# LDO_3V3.net
KiCad netlist of a schematic drawn in Altium Designer
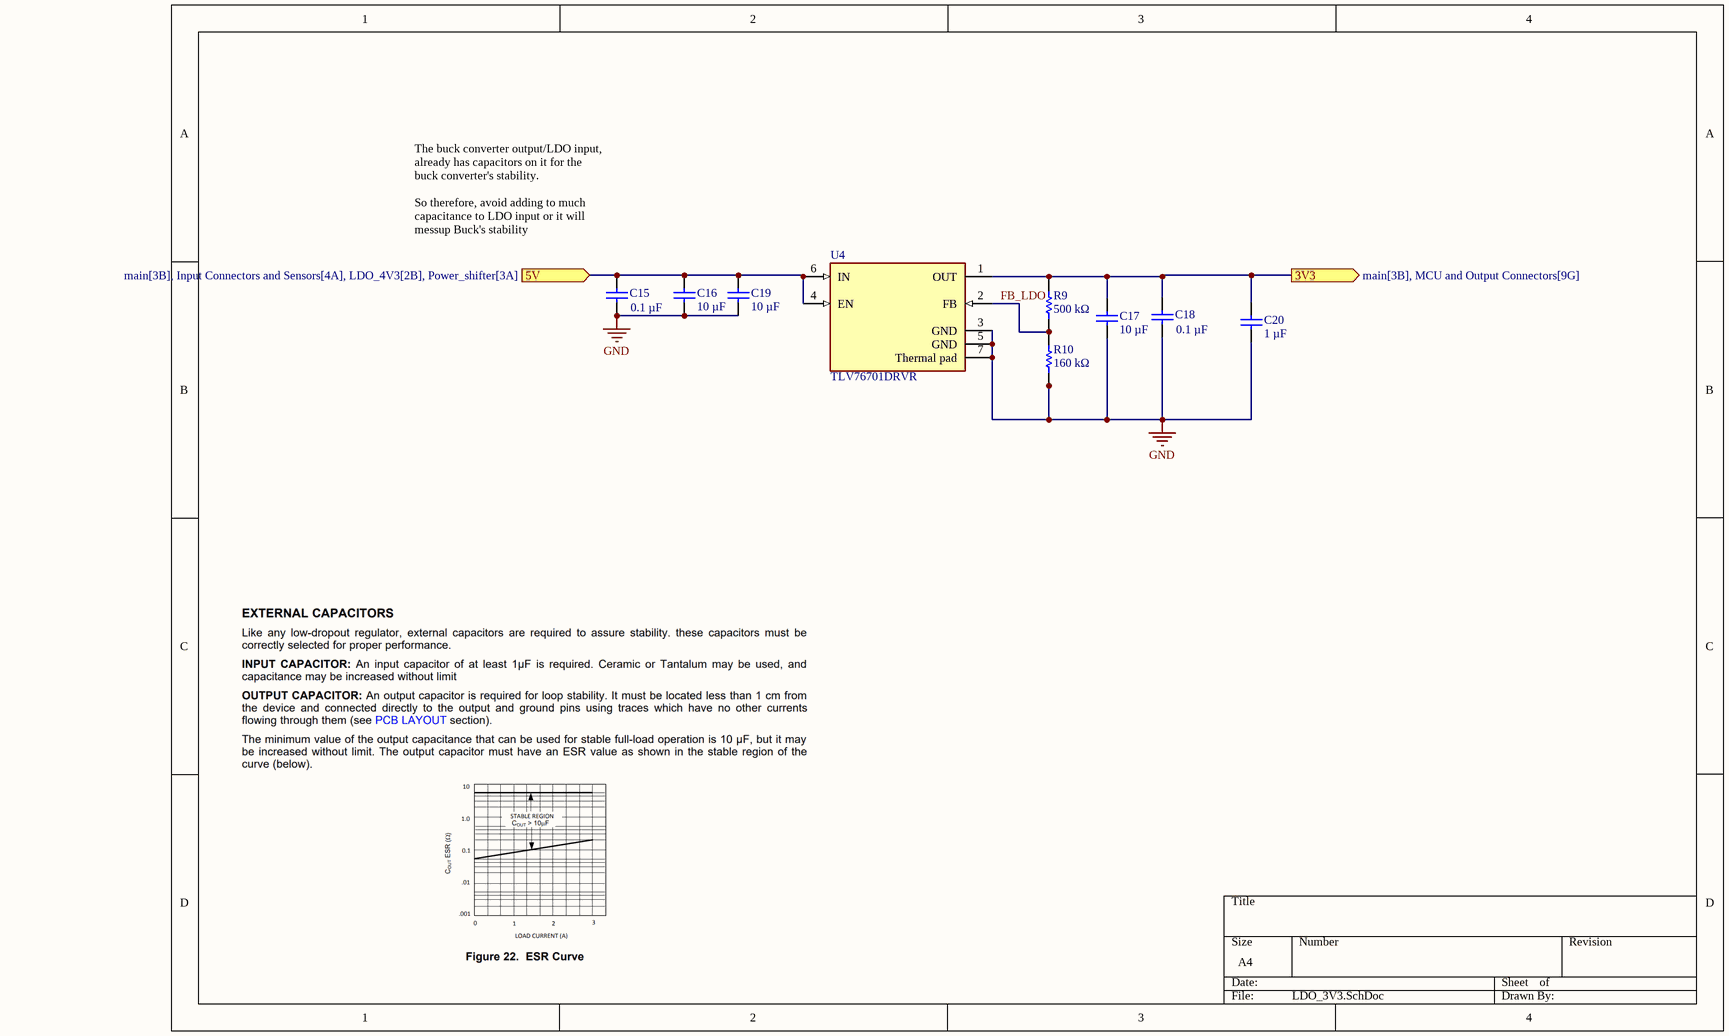
[diagram p0: LDO_3V3.SchDoc]

(export (version "E")
  (design (tool "Eeschema 10.0.6"))
  (components
    (comp (ref "C15")
      (value "0.1 µF")
      (footprint "0402_CAPC1005L")
      (description "Capacitor (Semiconductor SIM Model)")
      (fields (field (name "PUBLISHER") "Altium Limited"))
      (libsource (lib "MiscDev 3") (part "Cap Semi"))
    )
    (comp (ref "C16")
      (value "10 µF")
      (footprint "1210_CAPC3225L")
      (description "Capacitor (Semiconductor SIM Model)")
      (fields (field (name "PUBLISHER") "Altium Limited"))
      (libsource (lib "MiscDev 3") (part "Cap Semi"))
    )
    (comp (ref "C17")
      (value "10 µF")
      (footprint "1210_CAPC3225L")
      (description "Capacitor (Semiconductor SIM Model)")
      (fields (field (name "PUBLISHER") "Altium Limited"))
      (libsource (lib "MiscDev 3") (part "Cap Semi"))
    )
    (comp (ref "C18")
      (value "0.1 µF")
      (footprint "0402_CAPC1005L")
      (description "Capacitor (Semiconductor SIM Model)")
      (fields (field (name "PUBLISHER") "Altium Limited"))
      (libsource (lib "MiscDev 3") (part "Cap Semi"))
    )
    (comp (ref "C19")
      (value "10 µF")
      (footprint "1210_CAPC3225L")
      (description "Capacitor (Semiconductor SIM Model)")
      (fields (field (name "PUBLISHER") "Altium Limited"))
      (libsource (lib "MiscDev 3") (part "Cap Semi"))
    )
    (comp (ref "C20")
      (value "1 µF")
      (footprint "0603_CAPC1608L")
      (description "Capacitor (Semiconductor SIM Model)")
      (fields (field (name "PUBLISHER") "Altium Limited"))
      (libsource (lib "MiscDev 3") (part "Cap Semi"))
    )
    (comp (ref "R9")
      (value "500 kΩ")
      (footprint "0402_RESC1005L")
      (description "Semiconductor Resistor")
      (fields (field (name "Comment") "Res Semi") (field (name "PUBLISHER") "Altium Limited"))
      (libsource (lib "MiscDev 3") (part "Res Semi"))
    )
    (comp (ref "R10")
      (value "160 kΩ")
      (footprint "0402_RESC1005L")
      (description "Semiconductor Resistor")
      (fields (field (name "Comment") "Res Semi") (field (name "PUBLISHER") "Altium Limited"))
      (libsource (lib "MiscDev 3") (part "Res Semi"))
    )
    (comp (ref "U4")
      (value "TLV76701DRVR")
      (footprint "FP-DRV0006A-IPC_C")
      (description "IC REG LINEAR POS ADJ 1A 6WSON")
      (libsource (lib "Altium Content Vault") (part "02b25d0a349586096ecc9dc1ae98da2"))
    )
  )
  (nets
    (net (code "1") (name "/3V3") (class "Default")
      (node (ref "C17") (pin "1") (pinfunction "1_1") (pintype "passive"))
      (node (ref "C18") (pin "2") (pinfunction "2_2") (pintype "passive"))
      (node (ref "C20") (pin "1") (pinfunction "1_1") (pintype "passive"))
      (node (ref "R9") (pin "2") (pinfunction "2_2") (pintype "passive"))
      (node (ref "U4") (pin "1") (pinfunction "OUT_1") (pintype "power_in"))
    )
    (net (code "2") (name "/5V") (class "Default")
      (node (ref "C15") (pin "2") (pinfunction "2_2") (pintype "passive"))
      (node (ref "C16") (pin "1") (pinfunction "1_1") (pintype "passive"))
      (node (ref "C19") (pin "1") (pinfunction "1_1") (pintype "passive"))
      (node (ref "U4") (pin "4") (pinfunction "EN_4") (pintype "input"))
      (node (ref "U4") (pin "6") (pinfunction "IN_6") (pintype "input"))
    )
    (net (code "3") (name "/FB_LDO") (class "Default")
      (node (ref "R10") (pin "2") (pinfunction "2_2") (pintype "passive"))
      (node (ref "R9") (pin "1") (pinfunction "1_1") (pintype "passive"))
      (node (ref "U4") (pin "2") (pinfunction "FB_2") (pintype "input"))
    )
    (net (code "4") (name "GND") (class "Default")
      (node (ref "C15") (pin "1") (pinfunction "1_1") (pintype "passive"))
      (node (ref "C16") (pin "2") (pinfunction "2_2") (pintype "passive"))
      (node (ref "C17") (pin "2") (pinfunction "2_2") (pintype "passive"))
      (node (ref "C18") (pin "1") (pinfunction "1_1") (pintype "passive"))
      (node (ref "C19") (pin "2") (pinfunction "2_2") (pintype "passive"))
      (node (ref "C20") (pin "2") (pinfunction "2_2") (pintype "passive"))
      (node (ref "R10") (pin "1") (pinfunction "1_1") (pintype "passive"))
      (node (ref "U4") (pin "3") (pinfunction "GND_3") (pintype "power_in"))
      (node (ref "U4") (pin "5") (pinfunction "GND_5") (pintype "power_in"))
      (node (ref "U4") (pin "7") (pinfunction "Thermal_pad_7") (pintype "power_in"))
    )
  )
)
